# Constant_Current_Load.net
KiCad netlist of a schematic drawn in Altium Designer
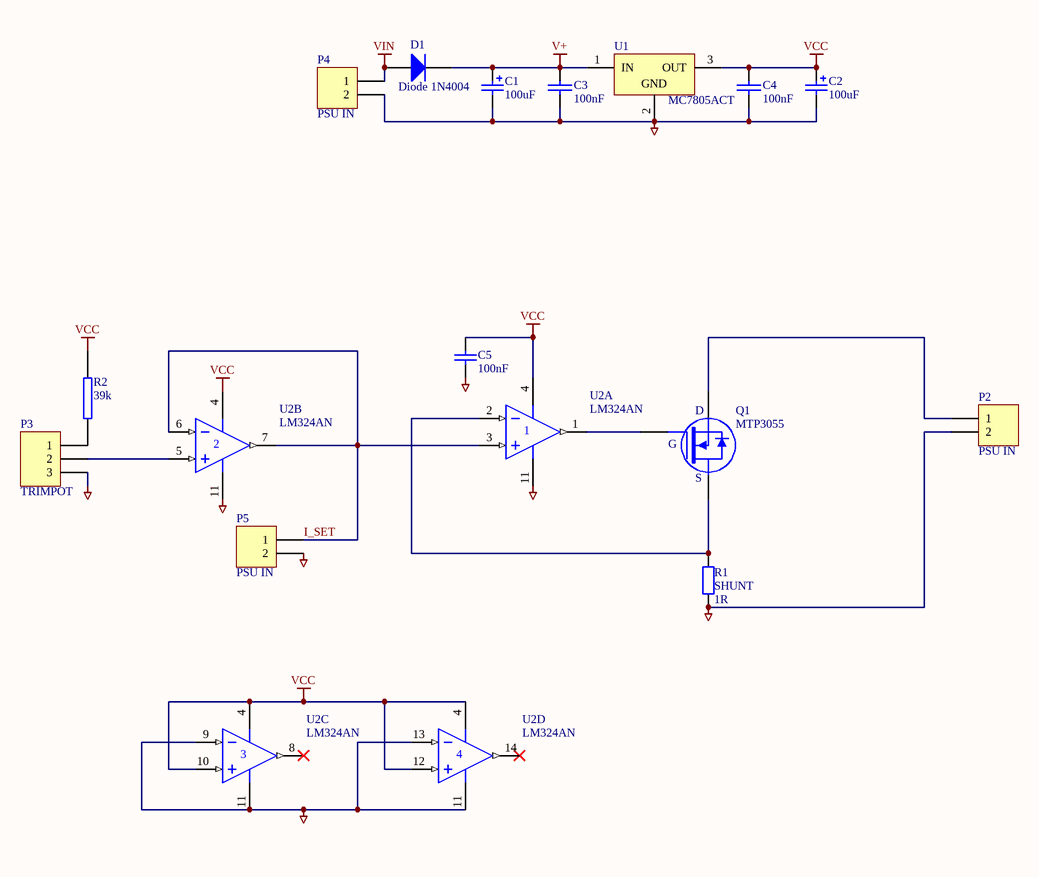
[diagram p0: Constant Current Load.SchDoc]

(export (version "E")
  (design (tool "Eeschema 10.0.6"))
  (components
    (comp (ref "C1")
      (value "100uF")
      (footprint "RB5-10.5")
      (description "CAPACITOR POLARISED TAG B CASE")
      (fields
        (field (name "MANUFACTURER") "Generic Components")
        (field (name "MOUSER PART NO.") "74-293D106X9020B8T")
      )
      (libsource (lib "Mi-Call Schematic") (part "Cap Pol"))
    )
    (comp (ref "C2")
      (value "100uF")
      (footprint "RB5-10.5")
      (description "CAPACITOR POLARISED TAG B CASE")
      (fields
        (field (name "MANUFACTURER") "Generic Components")
        (field (name "MOUSER PART NO.") "74-293D106X9020B8T")
      )
      (libsource (lib "Mi-Call Schematic") (part "Cap Pol"))
    )
    (comp (ref "C3")
      (value "100nF")
      (footprint "CAP (3D) - 0603")
      (description "CAPACITOR SMD 0603")
      (fields (field (name "MOUSER PART NO.") "81-GCM188R71C104KA7D") (field (name "MANUFACTURER") "Murata"))
      (libsource (lib "Mi-Call Schematic") (part "CAP"))
    )
    (comp (ref "C4")
      (value "100nF")
      (footprint "CAP (3D) - 0603")
      (description "CAPACITOR SMD 0603")
      (fields (field (name "MOUSER PART NO.") "81-GCM188R71C104KA7D") (field (name "MANUFACTURER") "Murata"))
      (libsource (lib "Mi-Call Schematic") (part "CAP"))
    )
    (comp (ref "C5")
      (value "100nF")
      (footprint "CAP (3D) - 0603")
      (description "Capacitor")
      (fields
        (field (name "MANUFACTURER") "YAEGO")
        (field (name "MANUFACTURER PART NO.") "CC0603ZRY5V9BB104")
      )
      (libsource (lib "Miscellaneous Devices") (part "Cap"))
    )
    (comp (ref "D1")
      (value "Diode 1N4004")
      (footprint "DO-41")
      (description "1 Amp General Purpose Rectifier")
      (fields (field (name "PUBLISHER") "Altium Limited"))
      (libsource (lib "Miscellaneous Devices") (part "Diode 1N4004"))
    )
    (comp (ref "P2")
      (value "PSU IN")
      (footprint "5.08mm HEADER 2 Way RA- With Socket")
      (description "Header, 2-Pin")
      (fields (field (name "PUBLISHER") "Altium Limited"))
      (libsource (lib "Miscellaneous Connectors") (part "Header 2"))
    )
    (comp (ref "P3")
      (value "TRIMPOT")
      (footprint "PCB POT")
      (description "Header, 3-Pin")
      (fields (field (name "PUBLISHER") "Altium Limited"))
      (libsource (lib "Miscellaneous Connectors") (part "Header 3"))
    )
    (comp (ref "P4")
      (value "PSU IN")
      (footprint "2 x 3.81mm RA")
      (description "Header, 2-Pin")
      (fields (field (name "PUBLISHER") "Altium Limited"))
      (libsource (lib "") (part "Header 2_1"))
    )
    (comp (ref "P5")
      (value "PSU IN")
      (footprint "HDR1X2")
      (description "Header, 2-Pin")
      (fields (field (name "PUBLISHER") "Altium Limited"))
      (libsource (lib "") (part "Header 2_1"))
    )
    (comp (ref "Q1")
      (value "MTP3055")
      (footprint "TO-220AB")
      (description "MTP3055 P-Channel MOSFET")
      (libsource (lib "NASCO") (part "MTP3055"))
    )
    (comp (ref "R1")
      (value "SHUNT")
      (footprint "5W WW")
      (description "Resistor")
      (fields (field (name "ALTIUM_VALUE") "1R") (field (name "PUBLISHER") "Altium Limited"))
      (libsource (lib "Miscellaneous Devices") (part "Res2"))
    )
    (comp (ref "R2")
      (value "39k")
      (footprint "RES (3D) - 0603")
      (description "RESISTOR SMD 0603")
      (fields
        (field (name "MOUSER PART NO.") "652-CR0603-JW-102ELF")
        (field (name "FARNELL PART NO.") "9331700")
      )
      (libsource (lib "NASCO Resistors") (part "RES SMD 0603 10k"))
    )
    (comp (ref "U1")
      (value "MC7805ACT")
      (footprint "TO-220AB")
      (description "3-Terminal Positive Fixed Voltage Regulator")
      (fields
        (field (name "MOUSER PART NO.") "512-LM7805ACT")
        (field (name "MANUFACTURER") "Fairchild Semiconductor")
      )
      (libsource (lib "Motorola Power Mgt Voltage Regulator") (part "MC7805ACT"))
    )
    (comp (ref "U2")
      (value "LM324AN")
      (footprint "DIP-14")
      (description "Quadruple Operational Amplifier")
      (fields (field (name "MANUFACTURER") "ST MICRO") (field (name "MOUSER PART NO.") "511-LM324AN"))
      (libsource (lib "TI Operational Amplifier") (part "LM324AN"))
    )
  )
  (nets
    (net (code "1") (name "/I_SET") (class "Default")
      (node (ref "P5") (pin "1") (pinfunction "1_1") (pintype "passive"))
      (node (ref "U2") (pin "3") (pinfunction "IN+_3") (pintype "input"))
      (node (ref "U2") (pin "6") (pinfunction "IN-_6") (pintype "input"))
      (node (ref "U2") (pin "7") (pinfunction "OUT_7") (pintype "output"))
    )
    (net (code "2") (name "GND") (class "Default")
      (node (ref "C1") (pin "2") (pinfunction "2_2") (pintype "passive"))
      (node (ref "C2") (pin "2") (pinfunction "2_2") (pintype "passive"))
      (node (ref "C3") (pin "2") (pinfunction "2_2") (pintype "passive"))
      (node (ref "C4") (pin "2") (pinfunction "2_2") (pintype "passive"))
      (node (ref "C5") (pin "1") (pinfunction "1_1") (pintype "passive"))
      (node (ref "P2") (pin "2") (pinfunction "2_2") (pintype "passive"))
      (node (ref "P3") (pin "3") (pinfunction "3_3") (pintype "passive"))
      (node (ref "P4") (pin "2") (pinfunction "2_2") (pintype "passive"))
      (node (ref "P5") (pin "2") (pinfunction "2_2") (pintype "passive"))
      (node (ref "R1") (pin "1") (pinfunction "1_1") (pintype "passive"))
      (node (ref "U1") (pin "2") (pinfunction "GND_2") (pintype "power_in"))
      (node (ref "U2") (pin "11") (pinfunction "V-_11") (pintype "power_in"))
      (node (ref "U2") (pin "13") (pinfunction "IN-_13") (pintype "input"))
      (node (ref "U2") (pin "9") (pinfunction "IN-_9") (pintype "input"))
    )
    (net (code "3") (name "Net-(P3-Pad1)") (class "Default")
      (node (ref "P3") (pin "1") (pinfunction "1_1") (pintype "passive"))
      (node (ref "R2") (pin "1") (pinfunction "1_1") (pintype "passive"))
    )
    (net (code "4") (name "Net-(Q1-D)") (class "Default")
      (node (ref "P2") (pin "1") (pinfunction "1_1") (pintype "passive"))
      (node (ref "Q1") (pin "2") (pinfunction "D_2") (pintype "passive"))
    )
    (net (code "5") (name "Net-(Q1-G)") (class "Default")
      (node (ref "Q1") (pin "1") (pinfunction "G_1") (pintype "passive"))
      (node (ref "U2") (pin "1") (pinfunction "OUT_1") (pintype "output"))
    )
    (net (code "6") (name "Net-(Q1-S)") (class "Default")
      (node (ref "Q1") (pin "3") (pinfunction "S_3") (pintype "passive"))
      (node (ref "R1") (pin "2") (pinfunction "2_2") (pintype "passive"))
      (node (ref "U2") (pin "2") (pinfunction "IN-_2") (pintype "input"))
    )
    (net (code "7") (name "Net-(U2B-IN+)") (class "Default")
      (node (ref "P3") (pin "2") (pinfunction "2_2") (pintype "passive"))
      (node (ref "U2") (pin "5") (pinfunction "IN+_5") (pintype "input"))
    )
    (net (code "8") (name "V+") (class "Default")
      (node (ref "C1") (pin "1") (pinfunction "1_1") (pintype "passive"))
      (node (ref "C3") (pin "1") (pinfunction "1_1") (pintype "passive"))
      (node (ref "D1") (pin "2") (pinfunction "K_2") (pintype "passive"))
      (node (ref "U1") (pin "1") (pinfunction "IN_1") (pintype "power_in"))
    )
    (net (code "9") (name "VCC") (class "Default")
      (node (ref "C2") (pin "1") (pinfunction "1_1") (pintype "passive"))
      (node (ref "C4") (pin "1") (pinfunction "1_1") (pintype "passive"))
      (node (ref "C5") (pin "2") (pinfunction "2_2") (pintype "passive"))
      (node (ref "R2") (pin "2") (pinfunction "2_2") (pintype "passive"))
      (node (ref "U1") (pin "3") (pinfunction "OUT_3") (pintype "power_in"))
      (node (ref "U2") (pin "10") (pinfunction "IN+_10") (pintype "input"))
      (node (ref "U2") (pin "12") (pinfunction "IN+_12") (pintype "input"))
      (node (ref "U2") (pin "4") (pinfunction "V+_4") (pintype "power_in"))
    )
    (net (code "10") (name "VIN") (class "Default")
      (node (ref "D1") (pin "1") (pinfunction "A_1") (pintype "passive"))
      (node (ref "P4") (pin "1") (pinfunction "1_1") (pintype "passive"))
    )
    (net (code "11") (name "unconnected-(U2C-OUT-Pad8)") (class "Default")
      (node (ref "U2") (pin "8") (pinfunction "OUT_8") (pintype "output+no_connect"))
    )
    (net (code "12") (name "unconnected-(U2D-OUT-Pad14)") (class "Default")
      (node (ref "U2") (pin "14") (pinfunction "OUT_14") (pintype "output+no_connect"))
    )
  )
)
